# ESP32_T_H_Interface.net
KiCad netlist of a schematic drawn in Altium Designer
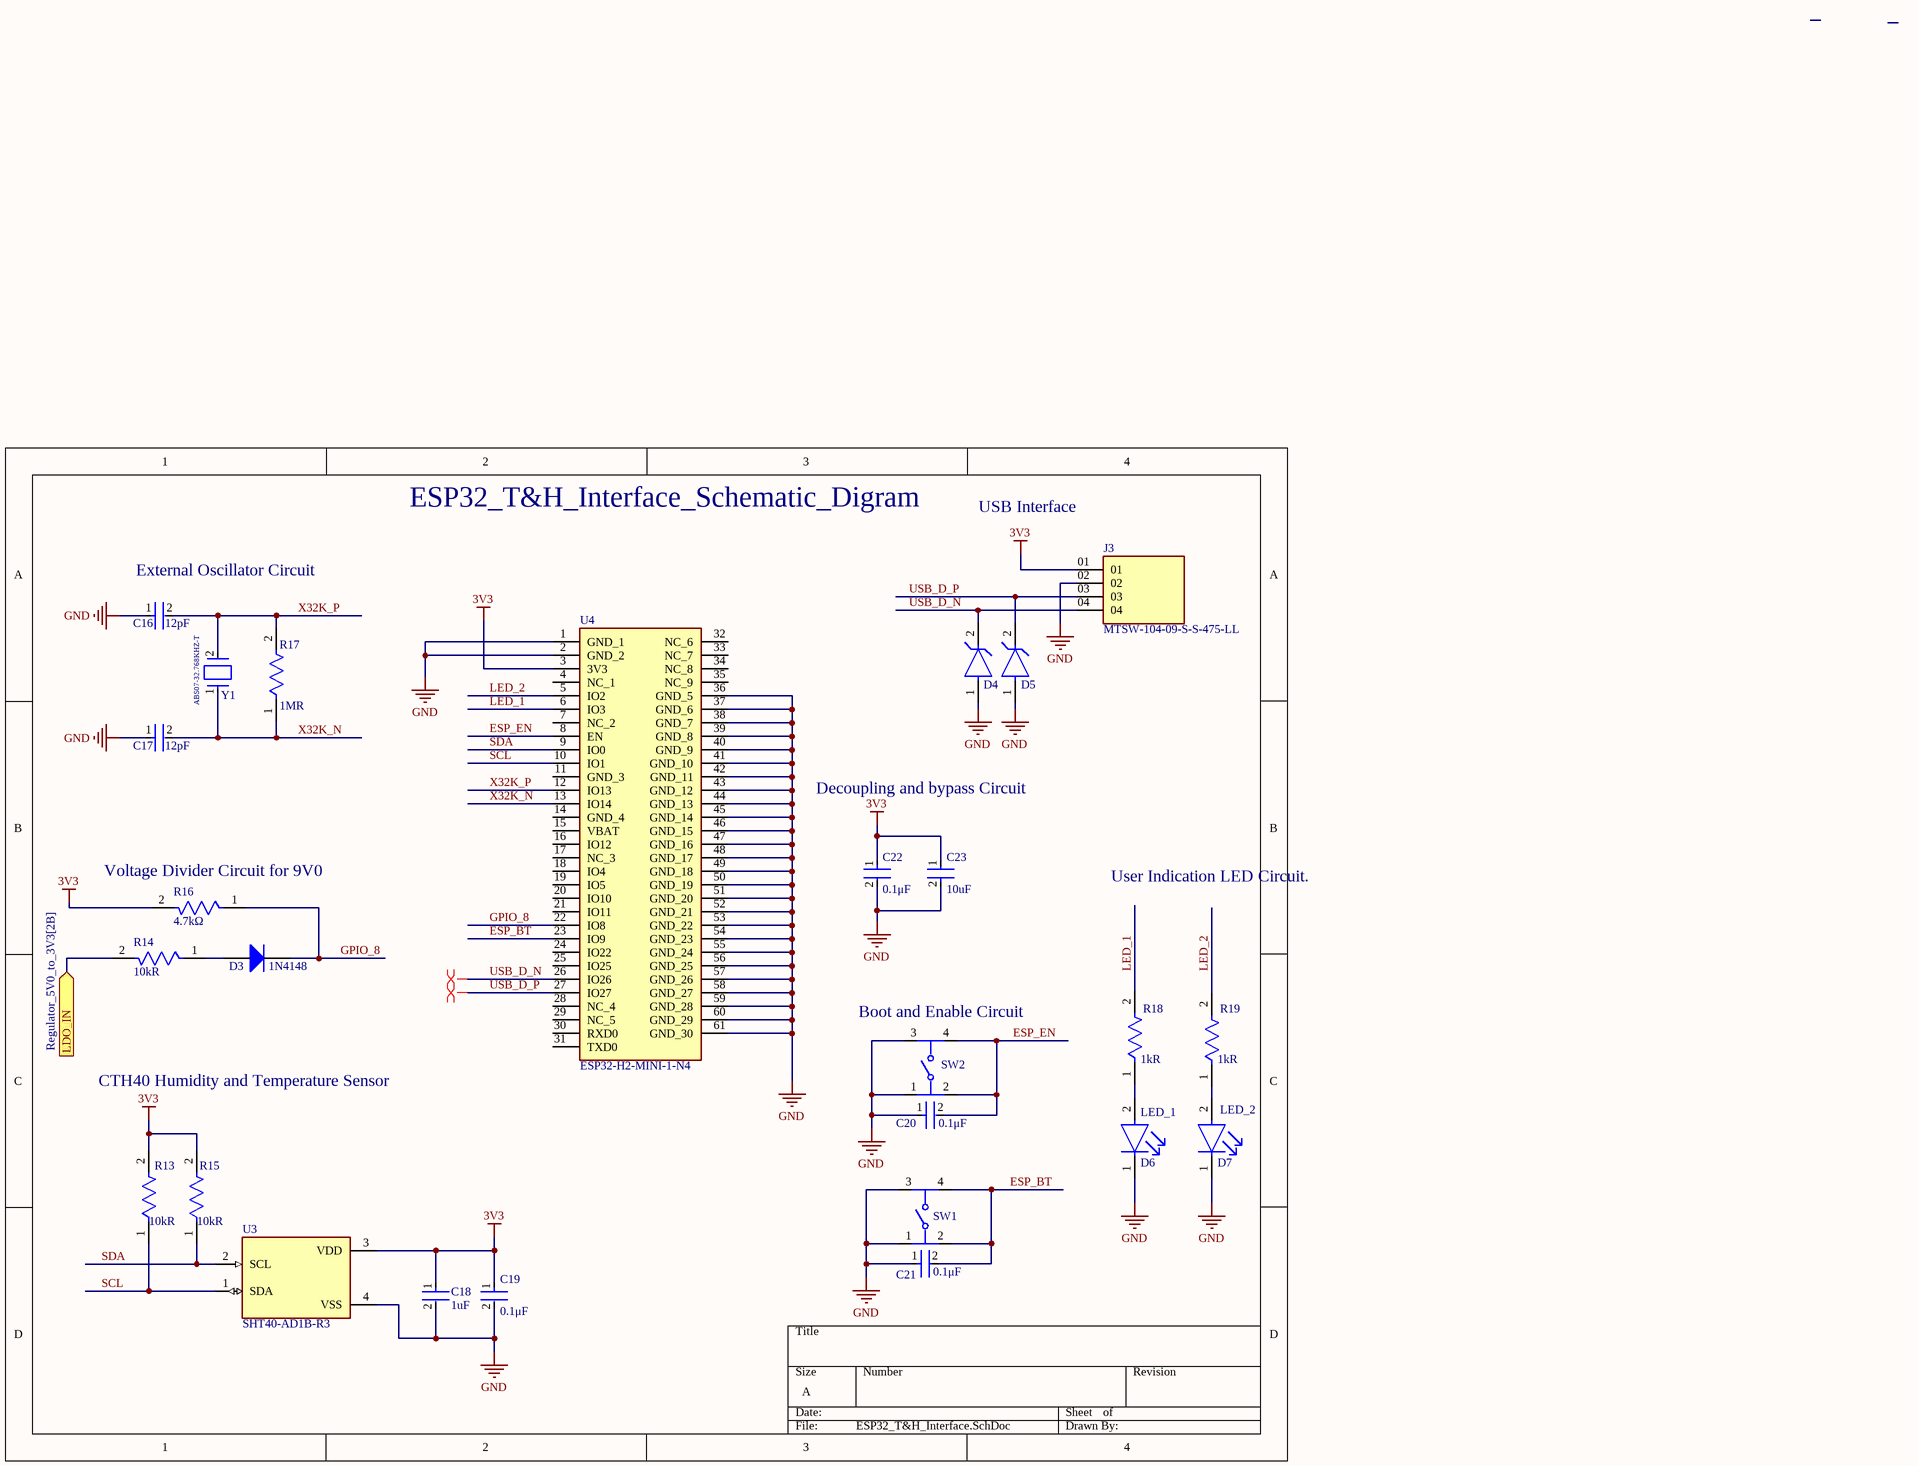
[diagram p0: ESP32_T&H_Interface.SchDoc]

(export (version "E")
  (design (tool "Eeschema 10.0.6"))
  (components
    (comp (ref "C16")
      (value "04025A120JAT2A")
      (footprint "FP-0402-L_1_0_1-W_0_5_0_1-IPC_B")
      (description "General Purpose Ceramic Capacitor, 0402, 12pF, 5%, C0G, 30ppm/°C, 50V")
      (fields
        (field (name "VOLTAGE") "50V")
        (field (name "CAPACITANCE") "12pF")
        (field (name "TOLERANCE") "5%")
      )
      (libsource (lib "Altium Content Vault") (part "b4654b650e69147ec39a6b967a45e02"))
    )
    (comp (ref "C17")
      (value "04025A120JAT2A")
      (footprint "FP-0402-L_1_0_1-W_0_5_0_1-IPC_B")
      (description "General Purpose Ceramic Capacitor, 0402, 12pF, 5%, C0G, 30ppm/°C, 50V")
      (fields
        (field (name "VOLTAGE") "50V")
        (field (name "CAPACITANCE") "12pF")
        (field (name "TOLERANCE") "5%")
      )
      (libsource (lib "Altium Content Vault") (part "b4654b650e69147ec39a6b967a45e02"))
    )
    (comp (ref "C18")
      (value "GRM155R61A105KE15D")
      (footprint "FP-GRM15-0_1-MFG")
      (description "CAP CER 1UF 10V X5R 0402")
      (fields
        (field (name "OCTOPART") "https://octopart.com/grm155r61a105ke15d-murata-197442")
        (field (name "MANUFACTURER") "Murata")
        (field (name "CAPACITANCE") "1uF")
      )
      (libsource (lib "Altium Content Vault") (part "02cd4be3c70576c341d710602a673aa"))
    )
    (comp (ref "C19")
      (value "C0603C104K8RACTU")
      (footprint "FP-C0603C-CF-MFG")
      (description "CAP CER 0.1UF 10V X7R 0603")
      (fields
        (field (name "TOLERANCE") "0.1")
        (field (name "OCTOPART") "https://octopart.com/c0603c104k8ractu-kemet-145075")
        (field (name "CAPACITANCE") "0.1μF")
      )
      (libsource (lib "Altium Content Vault") (part "b4654b650e69147ec39a6b967a45e02"))
    )
    (comp (ref "C20")
      (value "C0603C104K8RACTU")
      (footprint "FP-C0603C-CF-MFG")
      (description "CAP CER 0.1UF 10V X7R 0603")
      (fields
        (field (name "TOLERANCE") "0.1")
        (field (name "OCTOPART") "https://octopart.com/c0603c104k8ractu-kemet-145075")
        (field (name "CAPACITANCE") "0.1μF")
      )
      (libsource (lib "Altium Content Vault") (part "b4654b650e69147ec39a6b967a45e02"))
    )
    (comp (ref "C21")
      (value "C0603C104K8RACTU")
      (footprint "FP-C0603C-CF-MFG")
      (description "CAP CER 0.1UF 10V X7R 0603")
      (fields
        (field (name "TOLERANCE") "0.1")
        (field (name "OCTOPART") "https://octopart.com/c0603c104k8ractu-kemet-145075")
        (field (name "CAPACITANCE") "0.1μF")
      )
      (libsource (lib "Altium Content Vault") (part "b4654b650e69147ec39a6b967a45e02"))
    )
    (comp (ref "C22")
      (value "C0603C104K8RACTU")
      (footprint "FP-C0603C-CF-MFG")
      (description "CAP CER 0.1UF 10V X7R 0603")
      (fields
        (field (name "TOLERANCE") "0.1")
        (field (name "OCTOPART") "https://octopart.com/c0603c104k8ractu-kemet-145075")
        (field (name "CAPACITANCE") "0.1μF")
      )
      (libsource (lib "Altium Content Vault") (part "b4654b650e69147ec39a6b967a45e02"))
    )
    (comp (ref "C23")
      (value "C1608X5R1A106M080AC")
      (footprint "FP-C1608-080-0_1-IPC_A")
      (description "Multilayer Ceramic Capacitors 10μF ±20% 10V X5R SMD 0603")
      (fields (field (name "CAPACITANCE") "10uF") (field (name "TOLERANCE") "20%"))
      (libsource (lib "Altium Content Vault") (part "236180d848d6139a670b325ea6854c9"))
    )
    (comp (ref "D3")
      (value "1N4148")
      (footprint "DIOD-SOD323-2-A_V")
      (description "Fast Switching Diode, 75 V, 0.3 A, -65 to 150 degC, 2-Pin SOD323, RoHS, Tape and Reel")
      (libsource (lib "Altium Content Vault") (part "D-AK-2"))
    )
    (comp (ref "D4")
      (value "UCLAMP3601P.TNT")
      (footprint "FP-SLP1006P2-MFG")
      (description "TVS DIODE 33VWM 60VC SLP1006P2")
      (libsource (lib "Altium Content Vault") (part "3fba79ac723ca0a4e69928609483429"))
    )
    (comp (ref "D5")
      (value "UCLAMP3601P.TNT")
      (footprint "FP-SLP1006P2-MFG")
      (description "TVS DIODE 33VWM 60VC SLP1006P2")
      (libsource (lib "Altium Content Vault") (part "3fba79ac723ca0a4e69928609483429"))
    )
    (comp (ref "D6")
      (value "APHHS1005CGCK")
      (footprint "FP-APHHS1005CGCK-MFG")
      (description "LED GREEN CLEAR CHIP SMD")
      (libsource (lib "Altium Content Vault") (part "8706943c75ba83719d021d2fdc84c58"))
    )
    (comp (ref "D7")
      (value "APHHS1005CGCK")
      (footprint "FP-APHHS1005CGCK-MFG")
      (description "LED GREEN CLEAR CHIP SMD")
      (libsource (lib "Altium Content Vault") (part "8706943c75ba83719d021d2fdc84c58"))
    )
    (comp (ref "J3")
      (value "MTSW-104-09-S-S-475-LL")
      (footprint "SAMTEC_MTSW-104-09-S-S-475-LL")
      (libsource (lib "MTSW-104-09-S-S-475-LL") (part "MTSW-104-09-S-S-475-LL"))
    )
    (comp (ref "R13")
      (value "AC0402FR-0710KL")
      (footprint "FP-AC0402-MFG")
      (description "RES 10kΩ ±1% 0.063W 0402")
      (fields (field (name "TOLERANCE") "1%") (field (name "RESISTANCE") "10kR"))
      (libsource (lib "Altium Content Vault") (part "1029c3af85768c4190bb7ad29bc67b5"))
    )
    (comp (ref "R14")
      (value "AC0402FR-0710KL")
      (footprint "FP-AC0402-MFG")
      (description "RES 10kΩ ±1% 0.063W 0402")
      (fields (field (name "TOLERANCE") "1%") (field (name "RESISTANCE") "10kR"))
      (libsource (lib "Altium Content Vault") (part "1029c3af85768c4190bb7ad29bc67b5"))
    )
    (comp (ref "R15")
      (value "AC0402FR-0710KL")
      (footprint "FP-AC0402-MFG")
      (description "RES 10kΩ ±1% 0.063W 0402")
      (fields (field (name "TOLERANCE") "1%") (field (name "RESISTANCE") "10kR"))
      (libsource (lib "Altium Content Vault") (part "1029c3af85768c4190bb7ad29bc67b5"))
    )
    (comp (ref "R16")
      (value "RC0402JR-074K7L")
      (footprint "FP-RC0402-0_4-MFG")
      (fields (field (name "TOLERANCE") "5%") (field (name "RESISTANCE") "4.7kΩ"))
      (libsource (lib "Altium Content Vault") (part "RC0402JR-074K7L"))
    )
    (comp (ref "R17")
      (value "MCR01MRTF1004")
      (footprint "FP-MCR01-IPC_B")
      (description "Thick Film Chip Resistor, 0402, 1MΩ, 1%, 100ppm/°C, 0.063W, 50V")
      (fields (field (name "TOLERANCE") "1%") (field (name "RESISTANCE") "1MR"))
      (libsource (lib "Altium Content Vault") (part "1029c3af85768c4190bb7ad29bc67b5"))
    )
    (comp (ref "R18")
      (value "RMCF0402FT1K00")
      (footprint "FP-RMCF0402-MFG")
      (description "1kΩ ±1% 0.063W 0402 Thick Film Chip Resistor AEC-Q200 compliant")
      (fields (field (name "TOLERANCE") "1%") (field (name "RESISTANCE") "1kR"))
      (libsource (lib "Altium Content Vault") (part "1029c3af85768c4190bb7ad29bc67b5"))
    )
    (comp (ref "R19")
      (value "RMCF0402FT1K00")
      (footprint "FP-RMCF0402-MFG")
      (description "1kΩ ±1% 0.063W 0402 Thick Film Chip Resistor AEC-Q200 compliant")
      (fields (field (name "TOLERANCE") "1%") (field (name "RESISTANCE") "1kR"))
      (libsource (lib "Altium Content Vault") (part "1029c3af85768c4190bb7ad29bc67b5"))
    )
    (comp (ref "SW1")
      (value "KMR221NGLFS")
      (footprint "FP-KMR221NGLFS-0")
      (description "SWITCH TACTILE SPST-NO 0.05A 32V")
      (fields
        (field (name "MANUFACTURER") "C&K")
        (field (name "OCTOPART") "https://octopart.com/kmr221nglfs-c%26k+components-7203802")
      )
      (libsource (lib "Altium Content Vault") (part "b8895f3f4cefb76e1819d2863dba89b"))
    )
    (comp (ref "SW2")
      (value "KMR221NGLFS")
      (footprint "FP-KMR221NGLFS-0")
      (description "SWITCH TACTILE SPST-NO 0.05A 32V")
      (fields
        (field (name "MANUFACTURER") "C&K")
        (field (name "OCTOPART") "https://octopart.com/kmr221nglfs-c%26k+components-7203802")
      )
      (libsource (lib "Altium Content Vault") (part "b8895f3f4cefb76e1819d2863dba89b"))
    )
    (comp (ref "U3")
      (value "SHT40-AD1B-R3")
      (footprint "SHT4X")
      (fields (field (name "MF") "Sensirion"))
      (libsource (lib "SHT40-AD1B-R3") (part "SHT40-AD1B-R3"))
    )
    (comp (ref "U4")
      (value "ESP32-H2-MINI-1-N4")
      (footprint "ESP32H2MINI1N4")
      (description "Integrated Circuit")
      (fields (field (name "MOUSER PART NUMBER") "356-ESP32H2MINI1-N4"))
      (libsource (lib "ESP32-H2-MINI-1-N4") (part "ESP32-H2-MINI-1-N4"))
    )
    (comp (ref "Y1")
      (value "ABS07-32.768KHZ-T")
      (footprint "FP-ABS07-MFG")
      (description "Crystal 32.768kHz ±20ppm (Tol) 12.5pF FUND 70kΩ 2-Pin CSMD T/R")
      (fields (field (name "TOLERANCE") "20ppm"))
      (libsource (lib "Altium Content Vault") (part "c23a69dc6c9e2f18f2079038eb95dd1"))
    )
  )
  (nets
    (net (code "1") (name "/ESP_BT") (class "Default")
      (node (ref "C21") (pin "2") (pinfunction "2_2") (pintype "passive"))
      (node (ref "SW1") (pin "2") (pinfunction "2_2") (pintype "passive"))
      (node (ref "SW1") (pin "4") (pinfunction "4_4") (pintype "passive"))
      (node (ref "U4") (pin "23") (pinfunction "IO9_23") (pintype "passive"))
    )
    (net (code "2") (name "/ESP_EN") (class "Default")
      (node (ref "C20") (pin "2") (pinfunction "2_2") (pintype "passive"))
      (node (ref "SW2") (pin "2") (pinfunction "2_2") (pintype "passive"))
      (node (ref "SW2") (pin "4") (pinfunction "4_4") (pintype "passive"))
      (node (ref "U4") (pin "8") (pinfunction "EN_8") (pintype "passive"))
    )
    (net (code "3") (name "/GPIO_8") (class "Default")
      (node (ref "D3") (pin "2") (pinfunction "K_2") (pintype "passive"))
      (node (ref "R16") (pin "1") (pinfunction "1_1") (pintype "passive"))
      (node (ref "U4") (pin "22") (pinfunction "IO8_22") (pintype "passive"))
    )
    (net (code "4") (name "/LDO_IN") (class "Default")
      (node (ref "R14") (pin "2") (pinfunction "2_2") (pintype "passive"))
    )
    (net (code "5") (name "/LED_1") (class "Default")
      (node (ref "R18") (pin "2") (pinfunction "2_2") (pintype "passive"))
      (node (ref "U4") (pin "6") (pinfunction "IO3_6") (pintype "passive"))
    )
    (net (code "6") (name "/LED_2") (class "Default")
      (node (ref "R19") (pin "2") (pinfunction "2_2") (pintype "passive"))
      (node (ref "U4") (pin "5") (pinfunction "IO2_5") (pintype "passive"))
    )
    (net (code "7") (name "/SCL") (class "Default")
      (node (ref "R13") (pin "1") (pinfunction "1_1") (pintype "passive"))
      (node (ref "U3") (pin "1") (pinfunction "SDA_1") (pintype "bidirectional"))
      (node (ref "U4") (pin "10") (pinfunction "IO1_10") (pintype "passive"))
    )
    (net (code "8") (name "/SDA") (class "Default")
      (node (ref "R15") (pin "1") (pinfunction "1_1") (pintype "passive"))
      (node (ref "U3") (pin "2") (pinfunction "SCL_2") (pintype "input"))
      (node (ref "U4") (pin "9") (pinfunction "IO0_9") (pintype "passive"))
    )
    (net (code "9") (name "/USB_D_N") (class "Default")
      (node (ref "D4") (pin "2") (pinfunction "C_2") (pintype "passive"))
      (node (ref "J3") (pin "04") (pinfunction "04_04") (pintype "passive"))
      (node (ref "U4") (pin "26") (pinfunction "IO26_26") (pintype "passive"))
    )
    (net (code "10") (name "/USB_D_P") (class "Default")
      (node (ref "D5") (pin "2") (pinfunction "C_2") (pintype "passive"))
      (node (ref "J3") (pin "03") (pinfunction "03_03") (pintype "passive"))
      (node (ref "U4") (pin "27") (pinfunction "IO27_27") (pintype "passive"))
    )
    (net (code "11") (name "/X32K_N") (class "Default")
      (node (ref "C17") (pin "2") (pinfunction "2_2") (pintype "passive"))
      (node (ref "R17") (pin "1") (pinfunction "1_1") (pintype "passive"))
      (node (ref "U4") (pin "13") (pinfunction "IO14_13") (pintype "passive"))
      (node (ref "Y1") (pin "1") (pinfunction "1_1") (pintype "passive"))
    )
    (net (code "12") (name "/X32K_P") (class "Default")
      (node (ref "C16") (pin "2") (pinfunction "2_2") (pintype "passive"))
      (node (ref "R17") (pin "2") (pinfunction "2_2") (pintype "passive"))
      (node (ref "U4") (pin "12") (pinfunction "IO13_12") (pintype "passive"))
      (node (ref "Y1") (pin "2") (pinfunction "2_2") (pintype "passive"))
    )
    (net (code "13") (name "3V3") (class "Default")
      (node (ref "C18") (pin "1") (pinfunction "1_1") (pintype "passive"))
      (node (ref "C19") (pin "1") (pinfunction "1_1") (pintype "passive"))
      (node (ref "C22") (pin "1") (pinfunction "1_1") (pintype "passive"))
      (node (ref "C23") (pin "1") (pinfunction "1_1") (pintype "passive"))
      (node (ref "J3") (pin "01") (pinfunction "01_01") (pintype "passive"))
      (node (ref "R13") (pin "2") (pinfunction "2_2") (pintype "passive"))
      (node (ref "R15") (pin "2") (pinfunction "2_2") (pintype "passive"))
      (node (ref "R16") (pin "2") (pinfunction "2_2") (pintype "passive"))
      (node (ref "U3") (pin "3") (pinfunction "VDD_3") (pintype "power_in"))
      (node (ref "U4") (pin "3") (pinfunction "3V3_3") (pintype "passive"))
    )
    (net (code "14") (name "GND") (class "Default")
      (node (ref "C16") (pin "1") (pinfunction "1_1") (pintype "passive"))
      (node (ref "C17") (pin "1") (pinfunction "1_1") (pintype "passive"))
      (node (ref "C18") (pin "2") (pinfunction "2_2") (pintype "passive"))
      (node (ref "C19") (pin "2") (pinfunction "2_2") (pintype "passive"))
      (node (ref "C20") (pin "1") (pinfunction "1_1") (pintype "passive"))
      (node (ref "C21") (pin "1") (pinfunction "1_1") (pintype "passive"))
      (node (ref "C22") (pin "2") (pinfunction "2_2") (pintype "passive"))
      (node (ref "C23") (pin "2") (pinfunction "2_2") (pintype "passive"))
      (node (ref "D4") (pin "1") (pinfunction "A_1") (pintype "passive"))
      (node (ref "D5") (pin "1") (pinfunction "A_1") (pintype "passive"))
      (node (ref "D6") (pin "1") (pinfunction "C_1") (pintype "passive"))
      (node (ref "D7") (pin "1") (pinfunction "C_1") (pintype "passive"))
      (node (ref "J3") (pin "02") (pinfunction "02_02") (pintype "passive"))
      (node (ref "SW1") (pin "1") (pinfunction "1_1") (pintype "passive"))
      (node (ref "SW1") (pin "3") (pinfunction "3_3") (pintype "passive"))
      (node (ref "SW2") (pin "1") (pinfunction "1_1") (pintype "passive"))
      (node (ref "SW2") (pin "3") (pinfunction "3_3") (pintype "passive"))
      (node (ref "U3") (pin "4") (pinfunction "VSS_4") (pintype "power_in"))
      (node (ref "U4") (pin "1") (pinfunction "GND_1_1") (pintype "passive"))
      (node (ref "U4") (pin "2") (pinfunction "GND_2_2") (pintype "passive"))
      (node (ref "U4") (pin "36") (pinfunction "GND_5_36") (pintype "passive"))
      (node (ref "U4") (pin "37") (pinfunction "GND_6_37") (pintype "passive"))
      (node (ref "U4") (pin "38") (pinfunction "GND_7_38") (pintype "passive"))
      (node (ref "U4") (pin "39") (pinfunction "GND_8_39") (pintype "passive"))
      (node (ref "U4") (pin "40") (pinfunction "GND_9_40") (pintype "passive"))
      (node (ref "U4") (pin "41") (pinfunction "GND_10_41") (pintype "passive"))
      (node (ref "U4") (pin "42") (pinfunction "GND_11_42") (pintype "passive"))
      (node (ref "U4") (pin "43") (pinfunction "GND_12_43") (pintype "passive"))
      (node (ref "U4") (pin "44") (pinfunction "GND_13_44") (pintype "passive"))
      (node (ref "U4") (pin "45") (pinfunction "GND_14_45") (pintype "passive"))
      (node (ref "U4") (pin "46") (pinfunction "GND_15_46") (pintype "passive"))
      (node (ref "U4") (pin "47") (pinfunction "GND_16_47") (pintype "passive"))
      (node (ref "U4") (pin "48") (pinfunction "GND_17_48") (pintype "passive"))
      (node (ref "U4") (pin "49") (pinfunction "GND_18_49") (pintype "passive"))
      (node (ref "U4") (pin "50") (pinfunction "GND_19_50") (pintype "passive"))
      (node (ref "U4") (pin "51") (pinfunction "GND_20_51") (pintype "passive"))
      (node (ref "U4") (pin "52") (pinfunction "GND_21_52") (pintype "passive"))
      (node (ref "U4") (pin "53") (pinfunction "GND_22_53") (pintype "passive"))
      (node (ref "U4") (pin "54") (pinfunction "GND_23_54") (pintype "passive"))
      (node (ref "U4") (pin "55") (pinfunction "GND_24_55") (pintype "passive"))
      (node (ref "U4") (pin "56") (pinfunction "GND_25_56") (pintype "passive"))
      (node (ref "U4") (pin "57") (pinfunction "GND_26_57") (pintype "passive"))
      (node (ref "U4") (pin "58") (pinfunction "GND_27_58") (pintype "passive"))
      (node (ref "U4") (pin "59") (pinfunction "GND_28_59") (pintype "passive"))
      (node (ref "U4") (pin "60") (pinfunction "GND_29_60") (pintype "passive"))
      (node (ref "U4") (pin "61") (pinfunction "GND_30_61") (pintype "passive"))
    )
    (net (code "15") (name "Net-(D3-A)") (class "Default")
      (node (ref "D3") (pin "1") (pinfunction "A_1") (pintype "passive"))
      (node (ref "R14") (pin "1") (pinfunction "1_1") (pintype "passive"))
    )
    (net (code "16") (name "Net-(D6-A)") (class "Default")
      (node (ref "D6") (pin "2") (pinfunction "A_2") (pintype "passive"))
      (node (ref "R18") (pin "1") (pinfunction "1_1") (pintype "passive"))
    )
    (net (code "17") (name "Net-(D7-A)") (class "Default")
      (node (ref "D7") (pin "2") (pinfunction "A_2") (pintype "passive"))
      (node (ref "R19") (pin "1") (pinfunction "1_1") (pintype "passive"))
    )
    (net (code "18") (name "unconnected-(U4-GND_3-Pad11)") (class "Default")
      (node (ref "U4") (pin "11") (pinfunction "GND_3_11") (pintype "passive"))
    )
    (net (code "19") (name "unconnected-(U4-GND_4-Pad14)") (class "Default")
      (node (ref "U4") (pin "14") (pinfunction "GND_4_14") (pintype "passive"))
    )
    (net (code "20") (name "unconnected-(U4-IO4-Pad18)") (class "Default")
      (node (ref "U4") (pin "18") (pinfunction "IO4_18") (pintype "passive"))
    )
    (net (code "21") (name "unconnected-(U4-IO5-Pad19)") (class "Default")
      (node (ref "U4") (pin "19") (pinfunction "IO5_19") (pintype "passive"))
    )
    (net (code "22") (name "unconnected-(U4-IO10-Pad20)") (class "Default")
      (node (ref "U4") (pin "20") (pinfunction "IO10_20") (pintype "passive"))
    )
    (net (code "23") (name "unconnected-(U4-IO11-Pad21)") (class "Default")
      (node (ref "U4") (pin "21") (pinfunction "IO11_21") (pintype "passive"))
    )
    (net (code "24") (name "unconnected-(U4-IO12-Pad16)") (class "Default")
      (node (ref "U4") (pin "16") (pinfunction "IO12_16") (pintype "passive"))
    )
    (net (code "25") (name "unconnected-(U4-IO22-Pad24)") (class "Default")
      (node (ref "U4") (pin "24") (pinfunction "IO22_24") (pintype "passive"))
    )
    (net (code "26") (name "unconnected-(U4-IO25-Pad25)") (class "Default")
      (node (ref "U4") (pin "25") (pinfunction "IO25_25") (pintype "passive"))
    )
    (net (code "27") (name "unconnected-(U4-NC_1-Pad4)") (class "Default")
      (node (ref "U4") (pin "4") (pinfunction "NC_1_4") (pintype "passive"))
    )
    (net (code "28") (name "unconnected-(U4-NC_2-Pad7)") (class "Default")
      (node (ref "U4") (pin "7") (pinfunction "NC_2_7") (pintype "passive"))
    )
    (net (code "29") (name "unconnected-(U4-NC_3-Pad17)") (class "Default")
      (node (ref "U4") (pin "17") (pinfunction "NC_3_17") (pintype "passive"))
    )
    (net (code "30") (name "unconnected-(U4-NC_4-Pad28)") (class "Default")
      (node (ref "U4") (pin "28") (pinfunction "NC_4_28") (pintype "passive"))
    )
    (net (code "31") (name "unconnected-(U4-NC_5-Pad29)") (class "Default")
      (node (ref "U4") (pin "29") (pinfunction "NC_5_29") (pintype "passive"))
    )
    (net (code "32") (name "unconnected-(U4-NC_6-Pad32)") (class "Default")
      (node (ref "U4") (pin "32") (pinfunction "NC_6_32") (pintype "passive"))
    )
    (net (code "33") (name "unconnected-(U4-NC_7-Pad33)") (class "Default")
      (node (ref "U4") (pin "33") (pinfunction "NC_7_33") (pintype "passive"))
    )
    (net (code "34") (name "unconnected-(U4-NC_8-Pad34)") (class "Default")
      (node (ref "U4") (pin "34") (pinfunction "NC_8_34") (pintype "passive"))
    )
    (net (code "35") (name "unconnected-(U4-NC_9-Pad35)") (class "Default")
      (node (ref "U4") (pin "35") (pinfunction "NC_9_35") (pintype "passive"))
    )
    (net (code "36") (name "unconnected-(U4-RXD0-Pad30)") (class "Default")
      (node (ref "U4") (pin "30") (pinfunction "RXD0_30") (pintype "passive"))
    )
    (net (code "37") (name "unconnected-(U4-TXD0-Pad31)") (class "Default")
      (node (ref "U4") (pin "31") (pinfunction "TXD0_31") (pintype "passive"))
    )
    (net (code "38") (name "unconnected-(U4-VBAT-Pad15)") (class "Default")
      (node (ref "U4") (pin "15") (pinfunction "VBAT_15") (pintype "passive"))
    )
  )
)
